# white_noise.net
KiCad netlist of a schematic drawn in Altium Designer
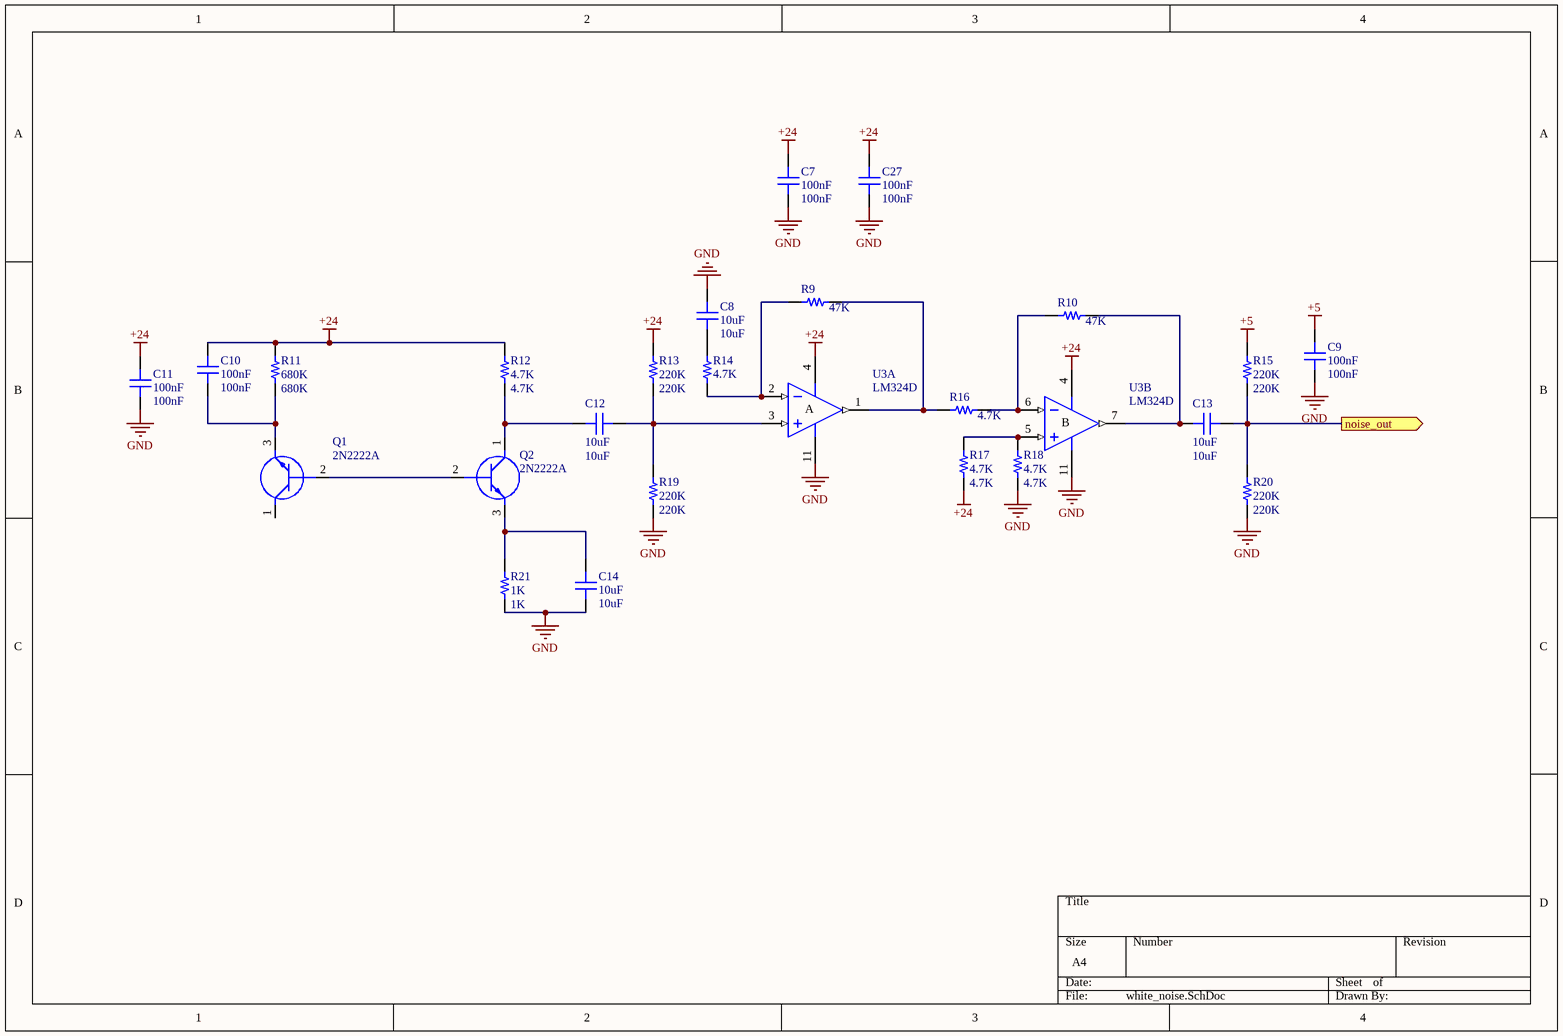
[diagram p0: white_noise.SchDoc]

(export (version "E")
  (design (tool "Eeschema 10.0.6"))
  (components
    (comp (ref "C7")
      (value "100nF")
      (footprint "cap805")
      (description "CAP SMD 0805")
      (fields (field (name "PART NUMBER") "C0805X106K9RAC7800") (field (name "ALTIUM_VALUE") "100nF"))
      (libsource (lib "lamp control-ver2") (part "Capacitor"))
    )
    (comp (ref "C8")
      (value "10uF")
      (footprint "cap805")
      (description "CAP SMD 0805")
      (fields (field (name "PART NUMBER") "C0805X106K9RAC7800") (field (name "ALTIUM_VALUE") "10uF"))
      (libsource (lib "lamp control-ver2") (part "Capacitor"))
    )
    (comp (ref "C9")
      (value "100nF")
      (footprint "cap805")
      (description "CAP SMD 0805")
      (fields (field (name "PART NUMBER") "C0805X106K9RAC7800") (field (name "ALTIUM_VALUE") "100nF"))
      (libsource (lib "lamp control-ver2") (part "Capacitor"))
    )
    (comp (ref "C10")
      (value "100nF")
      (footprint "cap805")
      (description "CAP SMD 0805")
      (fields (field (name "PART NUMBER") "C0805X106K9RAC7800") (field (name "ALTIUM_VALUE") "100nF"))
      (libsource (lib "lamp control-ver2") (part "Capacitor"))
    )
    (comp (ref "C11")
      (value "100nF")
      (footprint "cap805")
      (description "CAP SMD 0805")
      (fields (field (name "PART NUMBER") "C0805X106K9RAC7800") (field (name "ALTIUM_VALUE") "100nF"))
      (libsource (lib "lamp control-ver2") (part "Capacitor"))
    )
    (comp (ref "C12")
      (value "10uF")
      (footprint "cap805")
      (description "CAP SMD 0805")
      (fields (field (name "PART NUMBER") "C0805X106K9RAC7800") (field (name "ALTIUM_VALUE") "10uF"))
      (libsource (lib "lamp control-ver2") (part "Capacitor"))
    )
    (comp (ref "C13")
      (value "10uF")
      (footprint "cap805")
      (description "CAP SMD 0805")
      (fields (field (name "PART NUMBER") "C0805X106K9RAC7800") (field (name "ALTIUM_VALUE") "10uF"))
      (libsource (lib "lamp control-ver2") (part "Capacitor"))
    )
    (comp (ref "C14")
      (value "10uF")
      (footprint "cap805")
      (description "CAP SMD 0805")
      (fields (field (name "PART NUMBER") "C0805X106K9RAC7800") (field (name "ALTIUM_VALUE") "10uF"))
      (libsource (lib "lamp control-ver2") (part "Capacitor"))
    )
    (comp (ref "C27")
      (value "100nF")
      (footprint "cap805")
      (description "CAP SMD 0805")
      (fields (field (name "PART NUMBER") "C0805X106K9RAC7800") (field (name "ALTIUM_VALUE") "100nF"))
      (libsource (lib "lamp control-ver2") (part "Capacitor"))
    )
    (comp (ref "Q1")
      (value "2N2222A")
      (footprint "soT95p280x130-3n")
      (description "Transistor BJT NPN SMD")
      (libsource (lib "*") (part "2N2222A"))
    )
    (comp (ref "Q2")
      (value "2N2222A")
      (footprint "soT95p280x130-3n")
      (description "Transistor BJT NPN SMD")
      (libsource (lib "*") (part "2N2222A"))
    )
    (comp (ref "R9")
      (value "47K")
      (footprint "0603R")
      (description "RES SMD 0603")
      (fields (field (name "PART NUMBER") "RCS0805100KFKEA"))
      (libsource (lib "lamp control-ver2") (part "Resistor"))
    )
    (comp (ref "R10")
      (value "47K")
      (footprint "0603R")
      (description "RES SMD 0603")
      (fields (field (name "PART NUMBER") "RCS0805100KFKEA"))
      (libsource (lib "lamp control-ver2") (part "Resistor"))
    )
    (comp (ref "R11")
      (value "680K")
      (footprint "0603R")
      (description "RES SMD 0603")
      (fields (field (name "PART NUMBER") "RCS0805100KFKEA") (field (name "ALTIUM_VALUE") "680K"))
      (libsource (lib "lamp control-ver2") (part "Resistor"))
    )
    (comp (ref "R12")
      (value "4.7K")
      (footprint "0603R")
      (description "RES SMD 0603")
      (fields (field (name "PART NUMBER") "RCS0805100KFKEA") (field (name "ALTIUM_VALUE") "4.7K"))
      (libsource (lib "lamp control-ver2") (part "Resistor"))
    )
    (comp (ref "R13")
      (value "220K")
      (footprint "0603R")
      (description "RES SMD 0603")
      (fields (field (name "PART NUMBER") "RCS0805100KFKEA") (field (name "ALTIUM_VALUE") "220K"))
      (libsource (lib "lamp control-ver2") (part "Resistor"))
    )
    (comp (ref "R14")
      (value "4.7K")
      (footprint "0603R")
      (description "RES SMD 0603")
      (fields (field (name "PART NUMBER") "RCS0805100KFKEA"))
      (libsource (lib "lamp control-ver2") (part "Resistor"))
    )
    (comp (ref "R15")
      (value "220K")
      (footprint "0603R")
      (description "RES SMD 0603")
      (fields (field (name "PART NUMBER") "RCS0805100KFKEA") (field (name "ALTIUM_VALUE") "220K"))
      (libsource (lib "lamp control-ver2") (part "Resistor"))
    )
    (comp (ref "R16")
      (value "4.7K")
      (footprint "0603R")
      (description "RES SMD 0603")
      (fields (field (name "PART NUMBER") "RCS0805100KFKEA"))
      (libsource (lib "lamp control-ver2") (part "Resistor"))
    )
    (comp (ref "R17")
      (value "4.7K")
      (footprint "0603R")
      (description "RES SMD 0603")
      (fields (field (name "PART NUMBER") "RCS0805100KFKEA") (field (name "ALTIUM_VALUE") "4.7K"))
      (libsource (lib "lamp control-ver2") (part "Resistor"))
    )
    (comp (ref "R18")
      (value "4.7K")
      (footprint "0603R")
      (description "RES SMD 0603")
      (fields (field (name "PART NUMBER") "RCS0805100KFKEA") (field (name "ALTIUM_VALUE") "4.7K"))
      (libsource (lib "lamp control-ver2") (part "Resistor"))
    )
    (comp (ref "R19")
      (value "220K")
      (footprint "0603R")
      (description "RES SMD 0603")
      (fields (field (name "PART NUMBER") "RCS0805100KFKEA") (field (name "ALTIUM_VALUE") "220K"))
      (libsource (lib "lamp control-ver2") (part "Resistor"))
    )
    (comp (ref "R20")
      (value "220K")
      (footprint "0603R")
      (description "RES SMD 0603")
      (fields (field (name "PART NUMBER") "RCS0805100KFKEA") (field (name "ALTIUM_VALUE") "220K"))
      (libsource (lib "lamp control-ver2") (part "Resistor"))
    )
    (comp (ref "R21")
      (value "1K")
      (footprint "0603R")
      (description "RES SMD 0603")
      (fields (field (name "PART NUMBER") "RCS0805100KFKEA") (field (name "ALTIUM_VALUE") "1K"))
      (libsource (lib "lamp control-ver2") (part "Resistor"))
    )
    (comp (ref "U3")
      (value "LM324D")
      (footprint "SO14_N")
      (description "Low-Power Quad Operational Amplifier SMD")
      (fields (field (name "PUBLISHER") "Altium Limited"))
      (libsource (lib "ST Operational Amplifier") (part "LM324D"))
    )
  )
  (nets
    (net (code "1") (name "+5") (class "Default")
      (node (ref "C9") (pin "1") (pinfunction "1_1") (pintype "passive"))
      (node (ref "R15") (pin "2") (pinfunction "2_2") (pintype "passive"))
    )
    (net (code "2") (name "+24") (class "Default")
      (node (ref "C10") (pin "2") (pinfunction "2_2") (pintype "passive"))
      (node (ref "C11") (pin "1") (pinfunction "1_1") (pintype "passive"))
      (node (ref "C27") (pin "1") (pinfunction "1_1") (pintype "passive"))
      (node (ref "C7") (pin "1") (pinfunction "1_1") (pintype "passive"))
      (node (ref "R11") (pin "2") (pinfunction "2_2") (pintype "passive"))
      (node (ref "R12") (pin "2") (pinfunction "2_2") (pintype "passive"))
      (node (ref "R13") (pin "2") (pinfunction "2_2") (pintype "passive"))
      (node (ref "R17") (pin "1") (pinfunction "1_1") (pintype "passive"))
      (node (ref "U3") (pin "4") (pinfunction "V+_4") (pintype "power_in"))
    )
    (net (code "3") (name "/noise_out") (class "Default")
      (node (ref "C13") (pin "1") (pinfunction "1_1") (pintype "passive"))
      (node (ref "R15") (pin "1") (pinfunction "1_1") (pintype "passive"))
      (node (ref "R20") (pin "2") (pinfunction "2_2") (pintype "passive"))
    )
    (net (code "4") (name "GND") (class "Default")
      (node (ref "C11") (pin "2") (pinfunction "2_2") (pintype "passive"))
      (node (ref "C14") (pin "1") (pinfunction "1_1") (pintype "passive"))
      (node (ref "C27") (pin "2") (pinfunction "2_2") (pintype "passive"))
      (node (ref "C7") (pin "2") (pinfunction "2_2") (pintype "passive"))
      (node (ref "C8") (pin "1") (pinfunction "1_1") (pintype "passive"))
      (node (ref "C9") (pin "2") (pinfunction "2_2") (pintype "passive"))
      (node (ref "R18") (pin "1") (pinfunction "1_1") (pintype "passive"))
      (node (ref "R19") (pin "1") (pinfunction "1_1") (pintype "passive"))
      (node (ref "R20") (pin "1") (pinfunction "1_1") (pintype "passive"))
      (node (ref "R21") (pin "1") (pinfunction "1_1") (pintype "passive"))
      (node (ref "U3") (pin "11") (pinfunction "V-_11") (pintype "power_in"))
    )
    (net (code "5") (name "Net-(C8-Pad2)") (class "Default")
      (node (ref "C8") (pin "2") (pinfunction "2_2") (pintype "passive"))
      (node (ref "R14") (pin "2") (pinfunction "2_2") (pintype "passive"))
    )
    (net (code "6") (name "Net-(Q1-B)") (class "Default")
      (node (ref "Q1") (pin "2") (pinfunction "B_2") (pintype "passive"))
      (node (ref "Q2") (pin "2") (pinfunction "B_2") (pintype "passive"))
    )
    (net (code "7") (name "Net-(Q1-E)") (class "Default")
      (node (ref "C10") (pin "1") (pinfunction "1_1") (pintype "passive"))
      (node (ref "Q1") (pin "3") (pinfunction "E_3") (pintype "passive"))
      (node (ref "R11") (pin "1") (pinfunction "1_1") (pintype "passive"))
    )
    (net (code "8") (name "Net-(Q2-C)") (class "Default")
      (node (ref "C12") (pin "2") (pinfunction "2_2") (pintype "passive"))
      (node (ref "Q2") (pin "1") (pinfunction "C_1") (pintype "passive"))
      (node (ref "R12") (pin "1") (pinfunction "1_1") (pintype "passive"))
    )
    (net (code "9") (name "Net-(Q2-E)") (class "Default")
      (node (ref "C14") (pin "2") (pinfunction "2_2") (pintype "passive"))
      (node (ref "Q2") (pin "3") (pinfunction "E_3") (pintype "passive"))
      (node (ref "R21") (pin "2") (pinfunction "2_2") (pintype "passive"))
    )
    (net (code "10") (name "Net-(U3A-IN+)") (class "Default")
      (node (ref "C12") (pin "1") (pinfunction "1_1") (pintype "passive"))
      (node (ref "R13") (pin "1") (pinfunction "1_1") (pintype "passive"))
      (node (ref "R19") (pin "2") (pinfunction "2_2") (pintype "passive"))
      (node (ref "U3") (pin "3") (pinfunction "IN+_3") (pintype "input"))
    )
    (net (code "11") (name "Net-(U3A-IN-)") (class "Default")
      (node (ref "R14") (pin "1") (pinfunction "1_1") (pintype "passive"))
      (node (ref "R9") (pin "2") (pinfunction "2_2") (pintype "passive"))
      (node (ref "U3") (pin "2") (pinfunction "IN-_2") (pintype "input"))
    )
    (net (code "12") (name "Net-(U3A-OUT)") (class "Default")
      (node (ref "R16") (pin "2") (pinfunction "2_2") (pintype "passive"))
      (node (ref "R9") (pin "1") (pinfunction "1_1") (pintype "passive"))
      (node (ref "U3") (pin "1") (pinfunction "OUT_1") (pintype "output"))
    )
    (net (code "13") (name "Net-(U3B-IN+)") (class "Default")
      (node (ref "R17") (pin "2") (pinfunction "2_2") (pintype "passive"))
      (node (ref "R18") (pin "2") (pinfunction "2_2") (pintype "passive"))
      (node (ref "U3") (pin "5") (pinfunction "IN+_5") (pintype "input"))
    )
    (net (code "14") (name "Net-(U3B-IN-)") (class "Default")
      (node (ref "R10") (pin "2") (pinfunction "2_2") (pintype "passive"))
      (node (ref "R16") (pin "1") (pinfunction "1_1") (pintype "passive"))
      (node (ref "U3") (pin "6") (pinfunction "IN-_6") (pintype "input"))
    )
    (net (code "15") (name "Net-(U3B-OUT)") (class "Default")
      (node (ref "C13") (pin "2") (pinfunction "2_2") (pintype "passive"))
      (node (ref "R10") (pin "1") (pinfunction "1_1") (pintype "passive"))
      (node (ref "U3") (pin "7") (pinfunction "OUT_7") (pintype "output"))
    )
    (net (code "16") (name "unconnected-(Q1-C-Pad1)") (class "Default")
      (node (ref "Q1") (pin "1") (pinfunction "C_1") (pintype "passive"))
    )
  )
)
